# disinfection_device_control_system.net
KiCad netlist of a schematic drawn in EAGLE
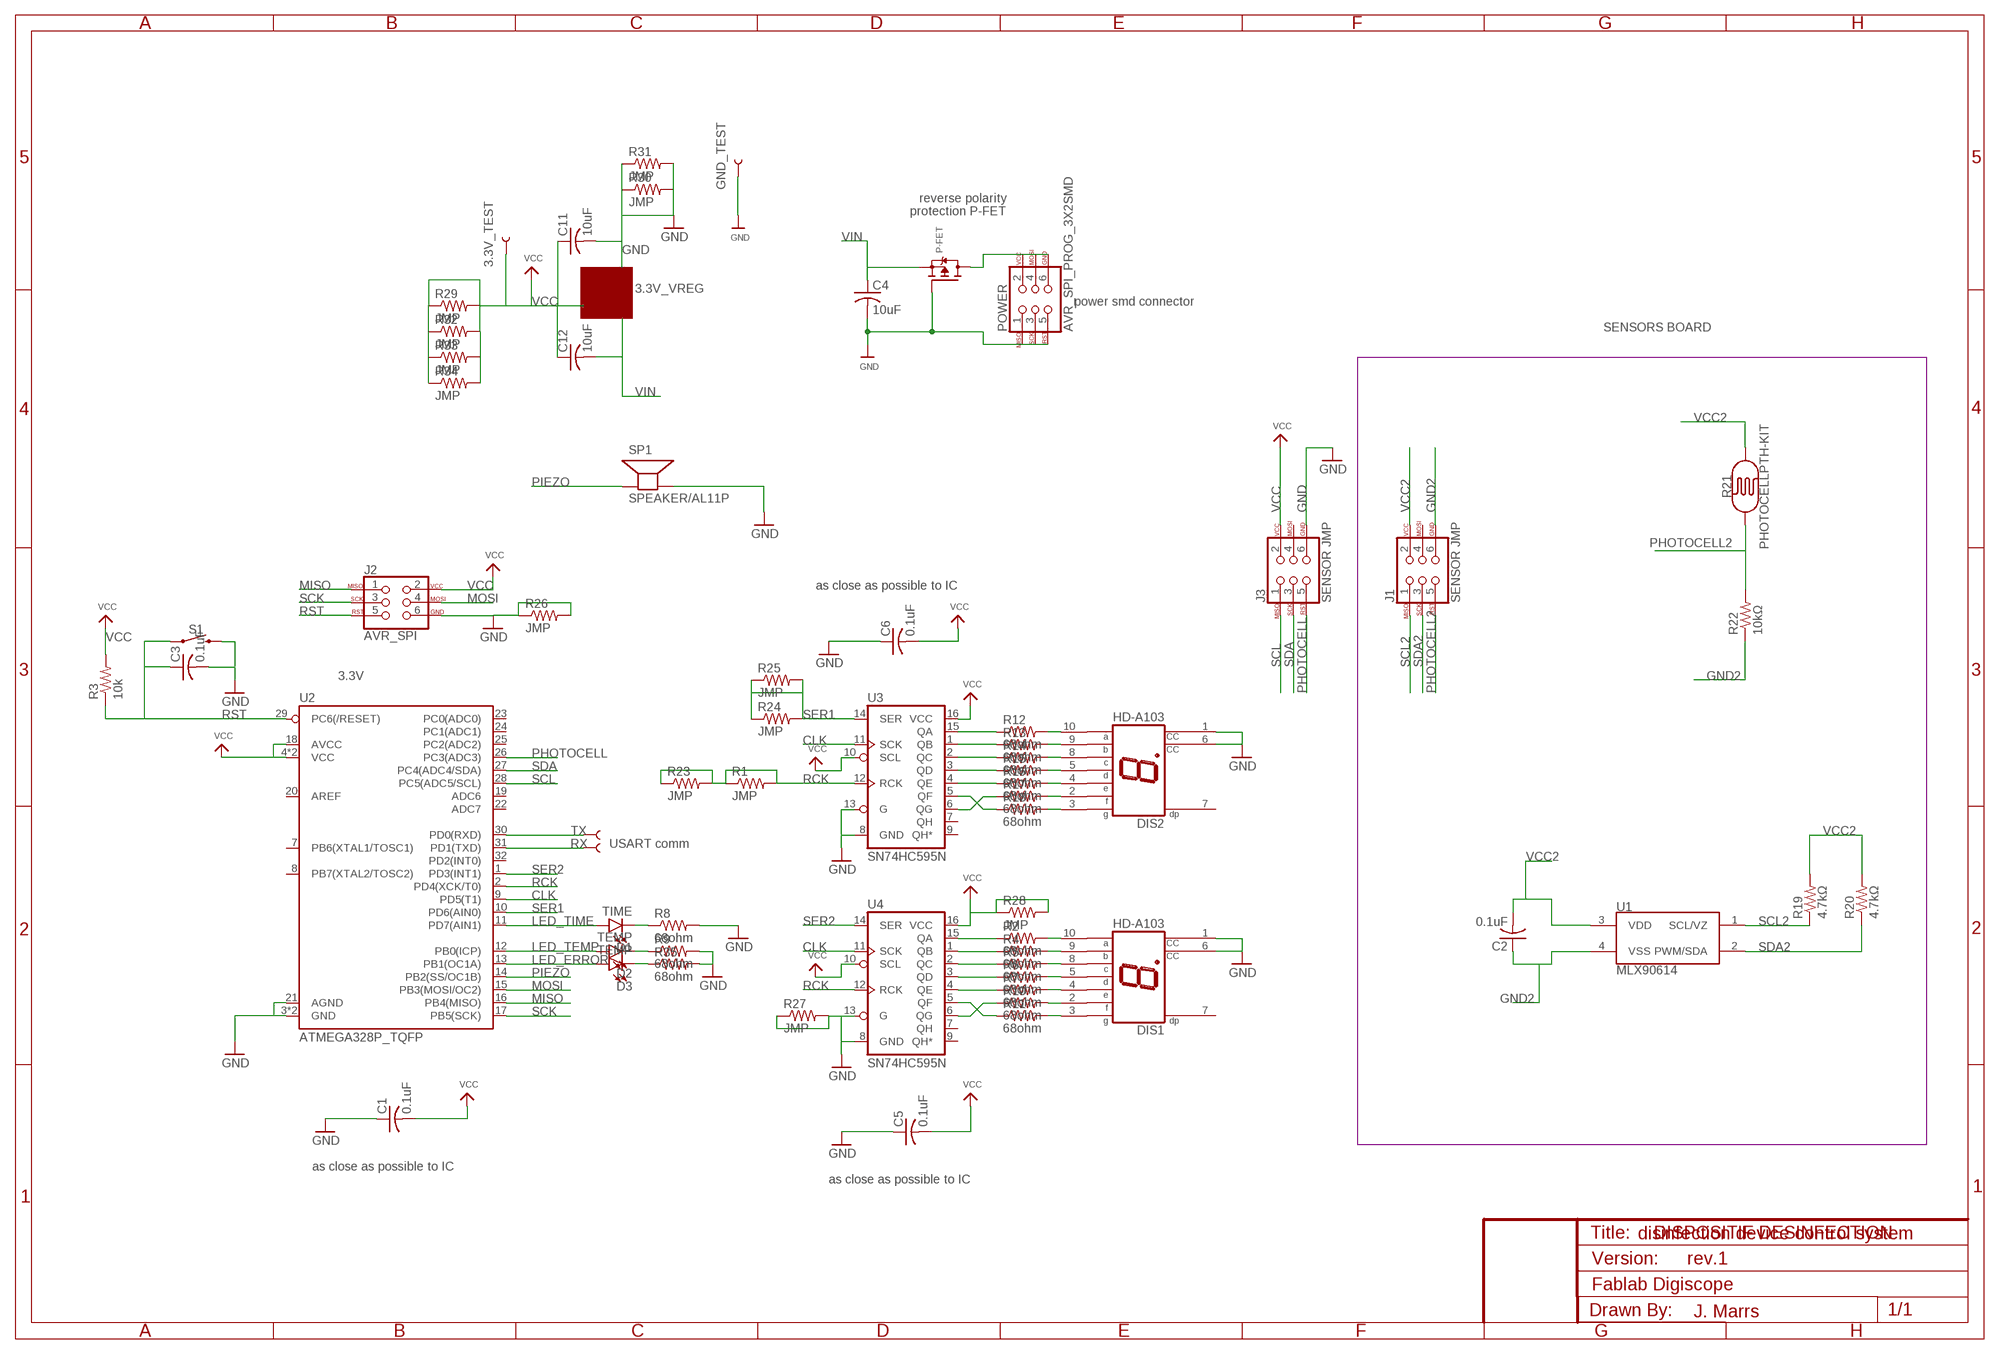
[diagram p0: schematic, sheet 1]

(export (version "E")
  (design (tool "Eeschema 10.0.6"))
  (components
    (comp (ref "3.3V_TEST")
      (value "TEST-POINT3")
      (footprint "eagle-import:PAD.03X.03")
      (libsource (lib "eagle-import") (part "TEST-POINT3"))
    )
    (comp (ref "3.3V_VREG")
      (value "MOSFET_PCH-DMG2305UX-7")
      (footprint "eagle-import:SOT23-3")
      (libsource (lib "eagle-import") (part "MOSFET_PCH-DMG2305UX-7"))
    )
    (comp (ref "C1")
      (value "0.1uF")
      (footprint "eagle-import:C1206")
      (libsource (lib "eagle-import") (part "C-USC1206"))
    )
    (comp (ref "C2")
      (value "0.1uF")
      (footprint "eagle-import:C1206")
      (libsource (lib "eagle-import") (part "C-USC1206"))
    )
    (comp (ref "C3")
      (value "0.1uF")
      (footprint "eagle-import:C1206")
      (libsource (lib "eagle-import") (part "C-USC1206"))
    )
    (comp (ref "C4")
      (value "10uF")
      (footprint "eagle-import:C1206")
      (libsource (lib "eagle-import") (part "C-USC1206"))
    )
    (comp (ref "C5")
      (value "0.1uF")
      (footprint "eagle-import:C1206")
      (libsource (lib "eagle-import") (part "C-USC1206"))
    )
    (comp (ref "C6")
      (value "0.1uF")
      (footprint "eagle-import:C1206")
      (libsource (lib "eagle-import") (part "C-USC1206"))
    )
    (comp (ref "C11")
      (value "10uF")
      (footprint "eagle-import:C1206")
      (libsource (lib "eagle-import") (part "C-USC1206"))
    )
    (comp (ref "C12")
      (value "10uF")
      (footprint "eagle-import:C1206")
      (libsource (lib "eagle-import") (part "C-USC1206"))
    )
    (comp (ref "D1")
      (value "TIME")
      (footprint "eagle-import:LED-1206")
      (libsource (lib "eagle-import") (part "LED-RED1206"))
    )
    (comp (ref "D2")
      (value "TEMP")
      (footprint "eagle-import:LED-1206")
      (libsource (lib "eagle-import") (part "LED-RED1206"))
    )
    (comp (ref "D3")
      (value "TEMP")
      (footprint "eagle-import:LED-1206")
      (libsource (lib "eagle-import") (part "LED-RED1206"))
    )
    (comp (ref "DIS1")
      (value "HD-A103")
      (footprint "eagle-import:HDSP-A")
      (libsource (lib "eagle-import") (part "HD-A103"))
    )
    (comp (ref "DIS2")
      (value "HD-A103")
      (footprint "eagle-import:HDSP-A")
      (libsource (lib "eagle-import") (part "HD-A103"))
    )
    (comp (ref "GND_TEST")
      (value "TEST-POINT3")
      (footprint "eagle-import:PAD.03X.03")
      (libsource (lib "eagle-import") (part "TEST-POINT3"))
    )
    (comp (ref "J1")
      (value "SENSOR JMP")
      (footprint "eagle-import:2X3_SMT_POSTS")
      (libsource (lib "eagle-import") (part "AVR_SPI_PROG_3X2SMD"))
    )
    (comp (ref "J2")
      (value "AVR_SPI")
      (footprint "eagle-import:2X3_SMT_POSTS")
      (libsource (lib "eagle-import") (part "AVR_SPI_PROG_3X2SMD"))
    )
    (comp (ref "J3")
      (value "SENSOR JMP")
      (footprint "eagle-import:2X3_SMT_POSTS")
      (libsource (lib "eagle-import") (part "AVR_SPI_PROG_3X2SMD"))
    )
    (comp (ref "P-FET")
      (value "MOSFET-PWIDE")
      (footprint "eagle-import:SOT23-WIDE")
      (libsource (lib "eagle-import") (part "MOSFET-PWIDE"))
    )
    (comp (ref "POWER")
      (value "AVR_SPI_PROG_3X2SMD")
      (footprint "eagle-import:2X3_SMT_POSTS")
      (libsource (lib "eagle-import") (part "AVR_SPI_PROG_3X2SMD"))
    )
    (comp (ref "R1")
      (value "JMP")
      (footprint "eagle-import:R1206")
      (libsource (lib "eagle-import") (part "R-US_R1206"))
    )
    (comp (ref "R2")
      (value "68ohm")
      (footprint "eagle-import:R1206")
      (libsource (lib "eagle-import") (part "R-US_R1206"))
    )
    (comp (ref "R3")
      (value "10k")
      (footprint "eagle-import:R1206")
      (libsource (lib "eagle-import") (part "R-US_R1206"))
    )
    (comp (ref "R4")
      (value "68ohm")
      (footprint "eagle-import:R1206")
      (libsource (lib "eagle-import") (part "R-US_R1206"))
    )
    (comp (ref "R5")
      (value "68ohm")
      (footprint "eagle-import:R1206")
      (libsource (lib "eagle-import") (part "R-US_R1206"))
    )
    (comp (ref "R6")
      (value "68ohm")
      (footprint "eagle-import:R1206")
      (libsource (lib "eagle-import") (part "R-US_R1206"))
    )
    (comp (ref "R7")
      (value "68ohm")
      (footprint "eagle-import:R1206")
      (libsource (lib "eagle-import") (part "R-US_R1206"))
    )
    (comp (ref "R8")
      (value "68ohm")
      (footprint "eagle-import:R1206")
      (libsource (lib "eagle-import") (part "R-US_R1206"))
    )
    (comp (ref "R9")
      (value "68ohm")
      (footprint "eagle-import:R1206")
      (libsource (lib "eagle-import") (part "R-US_R1206"))
    )
    (comp (ref "R10")
      (value "68ohm")
      (footprint "eagle-import:R1206")
      (libsource (lib "eagle-import") (part "R-US_R1206"))
    )
    (comp (ref "R11")
      (value "68ohm")
      (footprint "eagle-import:R1206")
      (libsource (lib "eagle-import") (part "R-US_R1206"))
    )
    (comp (ref "R12")
      (value "68ohm")
      (footprint "eagle-import:R1206")
      (libsource (lib "eagle-import") (part "R-US_R1206"))
    )
    (comp (ref "R13")
      (value "68ohm")
      (footprint "eagle-import:R1206")
      (libsource (lib "eagle-import") (part "R-US_R1206"))
    )
    (comp (ref "R14")
      (value "68ohm")
      (footprint "eagle-import:R1206")
      (libsource (lib "eagle-import") (part "R-US_R1206"))
    )
    (comp (ref "R15")
      (value "68ohm")
      (footprint "eagle-import:R1206")
      (libsource (lib "eagle-import") (part "R-US_R1206"))
    )
    (comp (ref "R16")
      (value "68ohm")
      (footprint "eagle-import:R1206")
      (libsource (lib "eagle-import") (part "R-US_R1206"))
    )
    (comp (ref "R17")
      (value "68ohm")
      (footprint "eagle-import:R1206")
      (libsource (lib "eagle-import") (part "R-US_R1206"))
    )
    (comp (ref "R18")
      (value "68ohm")
      (footprint "eagle-import:R1206")
      (libsource (lib "eagle-import") (part "R-US_R1206"))
    )
    (comp (ref "R19")
      (value "4.7kΩ")
      (footprint "eagle-import:R1206")
      (libsource (lib "eagle-import") (part "R-US_R1206"))
    )
    (comp (ref "R20")
      (value "4.7kΩ")
      (footprint "eagle-import:R1206")
      (libsource (lib "eagle-import") (part "R-US_R1206"))
    )
    (comp (ref "R21")
      (value "PHOTOCELLPTH-KIT")
      (footprint "eagle-import:PHOTOCELL-KIT")
      (libsource (lib "eagle-import") (part "PHOTOCELLPTH-KIT"))
    )
    (comp (ref "R22")
      (value "10kΩ")
      (footprint "eagle-import:R1206")
      (libsource (lib "eagle-import") (part "R-US_R1206"))
    )
    (comp (ref "R23")
      (value "JMP")
      (footprint "eagle-import:R1206")
      (libsource (lib "eagle-import") (part "R-US_R1206"))
    )
    (comp (ref "R24")
      (value "JMP")
      (footprint "eagle-import:R1206")
      (libsource (lib "eagle-import") (part "R-US_R1206"))
    )
    (comp (ref "R25")
      (value "JMP")
      (footprint "eagle-import:R1206")
      (libsource (lib "eagle-import") (part "R-US_R1206"))
    )
    (comp (ref "R26")
      (value "JMP")
      (footprint "eagle-import:R1206")
      (libsource (lib "eagle-import") (part "R-US_R1206"))
    )
    (comp (ref "R27")
      (value "JMP")
      (footprint "eagle-import:R1206")
      (libsource (lib "eagle-import") (part "R-US_R1206"))
    )
    (comp (ref "R28")
      (value "JMP")
      (footprint "eagle-import:R1206")
      (libsource (lib "eagle-import") (part "R-US_R1206"))
    )
    (comp (ref "R29")
      (value "JMP")
      (footprint "eagle-import:R1206")
      (libsource (lib "eagle-import") (part "R-US_R1206"))
    )
    (comp (ref "R30")
      (value "JMP")
      (footprint "eagle-import:R1206")
      (libsource (lib "eagle-import") (part "R-US_R1206"))
    )
    (comp (ref "R31")
      (value "JMP")
      (footprint "eagle-import:R1206")
      (libsource (lib "eagle-import") (part "R-US_R1206"))
    )
    (comp (ref "R32")
      (value "JMP")
      (footprint "eagle-import:R1206")
      (libsource (lib "eagle-import") (part "R-US_R1206"))
    )
    (comp (ref "R33")
      (value "JMP")
      (footprint "eagle-import:R1206")
      (libsource (lib "eagle-import") (part "R-US_R1206"))
    )
    (comp (ref "R34")
      (value "JMP")
      (footprint "eagle-import:R1206")
      (libsource (lib "eagle-import") (part "R-US_R1206"))
    )
    (comp (ref "R35")
      (value "68ohm")
      (footprint "eagle-import:R1206")
      (libsource (lib "eagle-import") (part "R-US_R1206"))
    )
    (comp (ref "RX")
      (value "TEST-POINT3")
      (footprint "eagle-import:PAD.03X.03")
      (libsource (lib "eagle-import") (part "TEST-POINT3"))
    )
    (comp (ref "S1")
      (value "MOMENTARY-SWITCH-SPST-PTH-6.0MM")
      (footprint "eagle-import:TACTILE_SWITCH_PTH_6.0MM")
      (libsource (lib "eagle-import") (part "MOMENTARY-SWITCH-SPST-PTH-6.0MM"))
    )
    (comp (ref "SP1")
      (value "SPEAKER/AL11P")
      (footprint "eagle-import:AL11P")
      (libsource (lib "eagle-import") (part "SPEAKER/AL11P"))
    )
    (comp (ref "TX")
      (value "TEST-POINT3")
      (footprint "eagle-import:PAD.03X.03")
      (libsource (lib "eagle-import") (part "TEST-POINT3"))
    )
    (comp (ref "U1")
      (value "MLX90614")
      (footprint "eagle-import:TO-39")
      (libsource (lib "eagle-import") (part "MLX90614"))
    )
    (comp (ref "U2")
      (value "ATMEGA328P_TQFP")
      (footprint "eagle-import:TQFP32-08")
      (libsource (lib "eagle-import") (part "ATMEGA328P_TQFP"))
    )
    (comp (ref "U3")
      (value "SN74HC595N")
      (footprint "eagle-import:DIP16")
      (libsource (lib "eagle-import") (part "74595NHC"))
    )
    (comp (ref "U4")
      (value "SN74HC595N")
      (footprint "eagle-import:DIP16")
      (libsource (lib "eagle-import") (part "74595NHC"))
    )
  )
  (nets
    (net (code "1") (name "/CLK") (class "Default")
      (node (ref "U2") (pin "9") (pinfunction "PD5(T1)_9") (pintype "bidirectional"))
      (node (ref "U3") (pin "11") (pinfunction "SCK_11") (pintype "input"))
      (node (ref "U4") (pin "11") (pinfunction "SCK_11") (pintype "input"))
    )
    (net (code "2") (name "/GND2") (class "Default")
      (node (ref "C2") (pin "1") (pinfunction "1_1") (pintype "passive"))
      (node (ref "J1") (pin "6") (pinfunction "6_6") (pintype "passive"))
      (node (ref "R22") (pin "1") (pinfunction "1_1") (pintype "passive"))
      (node (ref "U1") (pin "4") (pinfunction "VSS_4") (pintype "bidirectional"))
    )
    (net (code "3") (name "/LED_ERROR") (class "Default")
      (node (ref "D3") (pin "A") (pinfunction "A_A") (pintype "passive"))
      (node (ref "U2") (pin "13") (pinfunction "PB1(OC1A)_13") (pintype "bidirectional"))
    )
    (net (code "4") (name "/LED_TEMP") (class "Default")
      (node (ref "D2") (pin "A") (pinfunction "A_A") (pintype "passive"))
      (node (ref "U2") (pin "12") (pinfunction "PB0(ICP)_12") (pintype "bidirectional"))
    )
    (net (code "5") (name "/LED_TIME") (class "Default")
      (node (ref "D1") (pin "A") (pinfunction "A_A") (pintype "passive"))
      (node (ref "U2") (pin "11") (pinfunction "PD7(AIN1)_11") (pintype "bidirectional"))
    )
    (net (code "6") (name "/MISO") (class "Default")
      (node (ref "J2") (pin "1") (pinfunction "1_1") (pintype "passive"))
      (node (ref "U2") (pin "16") (pinfunction "PB4(MISO)_16") (pintype "bidirectional"))
    )
    (net (code "7") (name "/MOSI") (class "Default")
      (node (ref "J2") (pin "4") (pinfunction "4_4") (pintype "passive"))
      (node (ref "U2") (pin "15") (pinfunction "PB3(MOSI/OC2)_15") (pintype "bidirectional"))
    )
    (net (code "8") (name "/PHOTOCELL") (class "Default")
      (node (ref "J3") (pin "5") (pinfunction "5_5") (pintype "passive"))
      (node (ref "U2") (pin "26") (pinfunction "PC3(ADC3)_26") (pintype "bidirectional"))
    )
    (net (code "9") (name "/PHOTOCELL2") (class "Default")
      (node (ref "J1") (pin "5") (pinfunction "5_5") (pintype "passive"))
      (node (ref "R21") (pin "1") (pinfunction "P$1_1") (pintype "bidirectional"))
      (node (ref "R22") (pin "2") (pinfunction "2_2") (pintype "passive"))
    )
    (net (code "10") (name "/PIEZO") (class "Default")
      (node (ref "SP1") (pin "+") (pinfunction "+_+") (pintype "passive"))
      (node (ref "U2") (pin "14") (pinfunction "PB2(SS/OC1B)_14") (pintype "bidirectional"))
    )
    (net (code "11") (name "/RCK") (class "Default")
      (node (ref "R1") (pin "1") (pinfunction "1_1") (pintype "passive"))
      (node (ref "R1") (pin "2") (pinfunction "2_2") (pintype "passive"))
      (node (ref "R23") (pin "1") (pinfunction "1_1") (pintype "passive"))
      (node (ref "R23") (pin "2") (pinfunction "2_2") (pintype "passive"))
      (node (ref "U2") (pin "2") (pinfunction "PD4(XCK/T0)_2") (pintype "bidirectional"))
      (node (ref "U3") (pin "12") (pinfunction "RCK_12") (pintype "input"))
      (node (ref "U4") (pin "12") (pinfunction "RCK_12") (pintype "input"))
    )
    (net (code "12") (name "/RST") (class "Default")
      (node (ref "C3") (pin "1") (pinfunction "1_1") (pintype "passive"))
      (node (ref "J2") (pin "5") (pinfunction "5_5") (pintype "passive"))
      (node (ref "R3") (pin "1") (pinfunction "1_1") (pintype "passive"))
      (node (ref "S1") (pin "1") (pinfunction "1_1") (pintype "passive"))
      (node (ref "U2") (pin "29") (pinfunction "PC6(/RESET)_29") (pintype "bidirectional"))
    )
    (net (code "13") (name "/SCK") (class "Default")
      (node (ref "J2") (pin "3") (pinfunction "3_3") (pintype "passive"))
      (node (ref "U2") (pin "17") (pinfunction "PB5(SCK)_17") (pintype "bidirectional"))
    )
    (net (code "14") (name "/SCL") (class "Default")
      (node (ref "J3") (pin "1") (pinfunction "1_1") (pintype "passive"))
      (node (ref "U2") (pin "28") (pinfunction "PC5(ADC5/SCL)_28") (pintype "bidirectional"))
    )
    (net (code "15") (name "/SCL2") (class "Default")
      (node (ref "J1") (pin "1") (pinfunction "1_1") (pintype "passive"))
      (node (ref "R19") (pin "1") (pinfunction "1_1") (pintype "passive"))
      (node (ref "U1") (pin "1") (pinfunction "SCL/VZ_1") (pintype "bidirectional"))
    )
    (net (code "16") (name "/SDA") (class "Default")
      (node (ref "J3") (pin "3") (pinfunction "3_3") (pintype "passive"))
      (node (ref "U2") (pin "27") (pinfunction "PC4(ADC4/SDA)_27") (pintype "bidirectional"))
    )
    (net (code "17") (name "/SDA2") (class "Default")
      (node (ref "J1") (pin "3") (pinfunction "3_3") (pintype "passive"))
      (node (ref "R20") (pin "1") (pinfunction "1_1") (pintype "passive"))
      (node (ref "U1") (pin "2") (pinfunction "PWM/SDA_2") (pintype "bidirectional"))
    )
    (net (code "18") (name "/SER1") (class "Default")
      (node (ref "R24") (pin "1") (pinfunction "1_1") (pintype "passive"))
      (node (ref "R24") (pin "2") (pinfunction "2_2") (pintype "passive"))
      (node (ref "R25") (pin "1") (pinfunction "1_1") (pintype "passive"))
      (node (ref "R25") (pin "2") (pinfunction "2_2") (pintype "passive"))
      (node (ref "U2") (pin "10") (pinfunction "PD6(AIN0)_10") (pintype "bidirectional"))
      (node (ref "U3") (pin "14") (pinfunction "SER_14") (pintype "input"))
    )
    (net (code "19") (name "/SER2") (class "Default")
      (node (ref "U2") (pin "1") (pinfunction "PD3(INT1)_1") (pintype "bidirectional"))
      (node (ref "U4") (pin "14") (pinfunction "SER_14") (pintype "input"))
    )
    (net (code "20") (name "/VCC2") (class "Default")
      (node (ref "C2") (pin "2") (pinfunction "2_2") (pintype "passive"))
      (node (ref "J1") (pin "2") (pinfunction "2_2") (pintype "passive"))
      (node (ref "R19") (pin "2") (pinfunction "2_2") (pintype "passive"))
      (node (ref "R20") (pin "2") (pinfunction "2_2") (pintype "passive"))
      (node (ref "R21") (pin "2") (pinfunction "P$2_2") (pintype "bidirectional"))
      (node (ref "U1") (pin "3") (pinfunction "VDD_3") (pintype "bidirectional"))
    )
    (net (code "21") (name "/VIN") (class "Default")
      (node (ref "3.3V_VREG") (pin "2") (pinfunction "S_2") (pintype "bidirectional"))
      (node (ref "C12") (pin "2") (pinfunction "2_2") (pintype "passive"))
      (node (ref "C4") (pin "1") (pinfunction "1_1") (pintype "passive"))
      (node (ref "P-FET") (pin "2") (pinfunction "S_2") (pintype "passive"))
    )
    (net (code "22") (name "GND") (class "Default")
      (node (ref "3.3V_VREG") (pin "3") (pinfunction "D_3") (pintype "bidirectional"))
      (node (ref "C1") (pin "1") (pinfunction "1_1") (pintype "passive"))
      (node (ref "C11") (pin "2") (pinfunction "2_2") (pintype "passive"))
      (node (ref "C3") (pin "2") (pinfunction "2_2") (pintype "passive"))
      (node (ref "C4") (pin "2") (pinfunction "2_2") (pintype "passive"))
      (node (ref "C5") (pin "1") (pinfunction "1_1") (pintype "passive"))
      (node (ref "C6") (pin "1") (pinfunction "1_1") (pintype "passive"))
      (node (ref "DIS1") (pin "1") (pinfunction "CC_1") (pintype "passive"))
      (node (ref "DIS1") (pin "6") (pinfunction "CC_6") (pintype "passive"))
      (node (ref "DIS2") (pin "1") (pinfunction "CC_1") (pintype "passive"))
      (node (ref "DIS2") (pin "6") (pinfunction "CC_6") (pintype "passive"))
      (node (ref "GND_TEST") (pin "P$1") (pinfunction "1_P$1") (pintype "bidirectional"))
      (node (ref "J2") (pin "6") (pinfunction "6_6") (pintype "passive"))
      (node (ref "J3") (pin "6") (pinfunction "6_6") (pintype "passive"))
      (node (ref "P-FET") (pin "1") (pinfunction "G_1") (pintype "passive"))
      (node (ref "POWER") (pin "1") (pinfunction "1_1") (pintype "passive"))
      (node (ref "POWER") (pin "3") (pinfunction "3_3") (pintype "passive"))
      (node (ref "POWER") (pin "5") (pinfunction "5_5") (pintype "passive"))
      (node (ref "R26") (pin "1") (pinfunction "1_1") (pintype "passive"))
      (node (ref "R26") (pin "2") (pinfunction "2_2") (pintype "passive"))
      (node (ref "R27") (pin "1") (pinfunction "1_1") (pintype "passive"))
      (node (ref "R27") (pin "2") (pinfunction "2_2") (pintype "passive"))
      (node (ref "R30") (pin "1") (pinfunction "1_1") (pintype "passive"))
      (node (ref "R30") (pin "2") (pinfunction "2_2") (pintype "passive"))
      (node (ref "R31") (pin "1") (pinfunction "1_1") (pintype "passive"))
      (node (ref "R31") (pin "2") (pinfunction "2_2") (pintype "passive"))
      (node (ref "R35") (pin "2") (pinfunction "2_2") (pintype "passive"))
      (node (ref "R8") (pin "2") (pinfunction "2_2") (pintype "passive"))
      (node (ref "R9") (pin "2") (pinfunction "2_2") (pintype "passive"))
      (node (ref "S1") (pin "3") (pinfunction "2_3") (pintype "passive"))
      (node (ref "SP1") (pin "-") (pinfunction "-_-") (pintype "passive"))
      (node (ref "U2") (pin "21") (pinfunction "AGND_21") (pintype "bidirectional"))
      (node (ref "U2") (pin "3") (pinfunction "GND_3") (pintype "bidirectional"))
      (node (ref "U2") (pin "5") (pinfunction "GND_5") (pintype "bidirectional"))
      (node (ref "U3") (pin "13") (pinfunction "G_13") (pintype "input"))
      (node (ref "U3") (pin "8") (pinfunction "GND_8") (pintype "power_in"))
      (node (ref "U4") (pin "13") (pinfunction "G_13") (pintype "input"))
      (node (ref "U4") (pin "8") (pinfunction "GND_8") (pintype "power_in"))
    )
    (net (code "23") (name "Net-(D1-PadC)") (class "Default")
      (node (ref "D1") (pin "C") (pinfunction "C_C") (pintype "passive"))
      (node (ref "R8") (pin "1") (pinfunction "1_1") (pintype "passive"))
    )
    (net (code "24") (name "Net-(D2-PadC)") (class "Default")
      (node (ref "D2") (pin "C") (pinfunction "C_C") (pintype "passive"))
      (node (ref "R9") (pin "1") (pinfunction "1_1") (pintype "passive"))
    )
    (net (code "25") (name "Net-(D3-PadC)") (class "Default")
      (node (ref "D3") (pin "C") (pinfunction "C_C") (pintype "passive"))
      (node (ref "R35") (pin "1") (pinfunction "1_1") (pintype "passive"))
    )
    (net (code "26") (name "Net-(DIS1-A)") (class "Default")
      (node (ref "DIS1") (pin "10") (pinfunction "A_10") (pintype "passive"))
      (node (ref "R2") (pin "2") (pinfunction "2_2") (pintype "passive"))
    )
    (net (code "27") (name "Net-(DIS1-B)") (class "Default")
      (node (ref "DIS1") (pin "9") (pinfunction "B_9") (pintype "passive"))
      (node (ref "R4") (pin "2") (pinfunction "2_2") (pintype "passive"))
    )
    (net (code "28") (name "Net-(DIS1-C)") (class "Default")
      (node (ref "DIS1") (pin "8") (pinfunction "C_8") (pintype "passive"))
      (node (ref "R5") (pin "2") (pinfunction "2_2") (pintype "passive"))
    )
    (net (code "29") (name "Net-(DIS1-D)") (class "Default")
      (node (ref "DIS1") (pin "5") (pinfunction "D_5") (pintype "passive"))
      (node (ref "R6") (pin "2") (pinfunction "2_2") (pintype "passive"))
    )
    (net (code "30") (name "Net-(DIS1-E)") (class "Default")
      (node (ref "DIS1") (pin "4") (pinfunction "E_4") (pintype "passive"))
      (node (ref "R7") (pin "2") (pinfunction "2_2") (pintype "passive"))
    )
    (net (code "31") (name "Net-(DIS1-F)") (class "Default")
      (node (ref "DIS1") (pin "2") (pinfunction "F_2") (pintype "passive"))
      (node (ref "R10") (pin "2") (pinfunction "2_2") (pintype "passive"))
    )
    (net (code "32") (name "Net-(DIS1-G)") (class "Default")
      (node (ref "DIS1") (pin "3") (pinfunction "G_3") (pintype "passive"))
      (node (ref "R11") (pin "2") (pinfunction "2_2") (pintype "passive"))
    )
    (net (code "33") (name "Net-(DIS2-A)") (class "Default")
      (node (ref "DIS2") (pin "10") (pinfunction "A_10") (pintype "passive"))
      (node (ref "R12") (pin "2") (pinfunction "2_2") (pintype "passive"))
    )
    (net (code "34") (name "Net-(DIS2-B)") (class "Default")
      (node (ref "DIS2") (pin "9") (pinfunction "B_9") (pintype "passive"))
      (node (ref "R13") (pin "2") (pinfunction "2_2") (pintype "passive"))
    )
    (net (code "35") (name "Net-(DIS2-C)") (class "Default")
      (node (ref "DIS2") (pin "8") (pinfunction "C_8") (pintype "passive"))
      (node (ref "R14") (pin "2") (pinfunction "2_2") (pintype "passive"))
    )
    (net (code "36") (name "Net-(DIS2-D)") (class "Default")
      (node (ref "DIS2") (pin "5") (pinfunction "D_5") (pintype "passive"))
      (node (ref "R15") (pin "2") (pinfunction "2_2") (pintype "passive"))
    )
    (net (code "37") (name "Net-(DIS2-E)") (class "Default")
      (node (ref "DIS2") (pin "4") (pinfunction "E_4") (pintype "passive"))
      (node (ref "R16") (pin "2") (pinfunction "2_2") (pintype "passive"))
    )
    (net (code "38") (name "Net-(DIS2-F)") (class "Default")
      (node (ref "DIS2") (pin "2") (pinfunction "F_2") (pintype "passive"))
      (node (ref "R17") (pin "2") (pinfunction "2_2") (pintype "passive"))
    )
    (net (code "39") (name "Net-(DIS2-G)") (class "Default")
      (node (ref "DIS2") (pin "3") (pinfunction "G_3") (pintype "passive"))
      (node (ref "R18") (pin "2") (pinfunction "2_2") (pintype "passive"))
    )
    (net (code "40") (name "Net-(P-FET-D)") (class "Default")
      (node (ref "P-FET") (pin "3") (pinfunction "D_3") (pintype "passive"))
      (node (ref "POWER") (pin "2") (pinfunction "2_2") (pintype "passive"))
      (node (ref "POWER") (pin "4") (pinfunction "4_4") (pintype "passive"))
      (node (ref "POWER") (pin "6") (pinfunction "6_6") (pintype "passive"))
    )
    (net (code "41") (name "Net-(RX-1)") (class "Default")
      (node (ref "RX") (pin "P$1") (pinfunction "1_P$1") (pintype "bidirectional"))
      (node (ref "U2") (pin "31") (pinfunction "PD1(TXD)_31") (pintype "bidirectional"))
    )
    (net (code "42") (name "Net-(TX-1)") (class "Default")
      (node (ref "TX") (pin "P$1") (pinfunction "1_P$1") (pintype "bidirectional"))
      (node (ref "U2") (pin "30") (pinfunction "PD0(RXD)_30") (pintype "bidirectional"))
    )
    (net (code "43") (name "Net-(U3-QA)") (class "Default")
      (node (ref "R12") (pin "1") (pinfunction "1_1") (pintype "passive"))
      (node (ref "U3") (pin "15") (pinfunction "QA_15") (pintype "tri_state"))
    )
    (net (code "44") (name "Net-(U3-QB)") (class "Default")
      (node (ref "R13") (pin "1") (pinfunction "1_1") (pintype "passive"))
      (node (ref "U3") (pin "1") (pinfunction "QB_1") (pintype "tri_state"))
    )
    (net (code "45") (name "Net-(U3-QC)") (class "Default")
      (node (ref "R14") (pin "1") (pinfunction "1_1") (pintype "passive"))
      (node (ref "U3") (pin "2") (pinfunction "QC_2") (pintype "tri_state"))
    )
    (net (code "46") (name "Net-(U3-QD)") (class "Default")
      (node (ref "R15") (pin "1") (pinfunction "1_1") (pintype "passive"))
      (node (ref "U3") (pin "3") (pinfunction "QD_3") (pintype "tri_state"))
    )
    (net (code "47") (name "Net-(U3-QE)") (class "Default")
      (node (ref "R16") (pin "1") (pinfunction "1_1") (pintype "passive"))
      (node (ref "U3") (pin "4") (pinfunction "QE_4") (pintype "tri_state"))
    )
    (net (code "48") (name "Net-(U3-QF)") (class "Default")
      (node (ref "R18") (pin "1") (pinfunction "1_1") (pintype "passive"))
      (node (ref "U3") (pin "5") (pinfunction "QF_5") (pintype "tri_state"))
    )
    (net (code "49") (name "Net-(U3-QG)") (class "Default")
      (node (ref "R17") (pin "1") (pinfunction "1_1") (pintype "passive"))
      (node (ref "U3") (pin "6") (pinfunction "QG_6") (pintype "tri_state"))
    )
    (net (code "50") (name "Net-(U4-QA)") (class "Default")
      (node (ref "R2") (pin "1") (pinfunction "1_1") (pintype "passive"))
      (node (ref "U4") (pin "15") (pinfunction "QA_15") (pintype "tri_state"))
    )
    (net (code "51") (name "Net-(U4-QB)") (class "Default")
      (node (ref "R4") (pin "1") (pinfunction "1_1") (pintype "passive"))
      (node (ref "U4") (pin "1") (pinfunction "QB_1") (pintype "tri_state"))
    )
    (net (code "52") (name "Net-(U4-QC)") (class "Default")
      (node (ref "R5") (pin "1") (pinfunction "1_1") (pintype "passive"))
      (node (ref "U4") (pin "2") (pinfunction "QC_2") (pintype "tri_state"))
    )
    (net (code "53") (name "Net-(U4-QD)") (class "Default")
      (node (ref "R6") (pin "1") (pinfunction "1_1") (pintype "passive"))
      (node (ref "U4") (pin "3") (pinfunction "QD_3") (pintype "tri_state"))
    )
    (net (code "54") (name "Net-(U4-QE)") (class "Default")
      (node (ref "R7") (pin "1") (pinfunction "1_1") (pintype "passive"))
      (node (ref "U4") (pin "4") (pinfunction "QE_4") (pintype "tri_state"))
    )
    (net (code "55") (name "Net-(U4-QF)") (class "Default")
      (node (ref "R11") (pin "1") (pinfunction "1_1") (pintype "passive"))
      (node (ref "U4") (pin "5") (pinfunction "QF_5") (pintype "tri_state"))
    )
    (net (code "56") (name "Net-(U4-QG)") (class "Default")
      (node (ref "R10") (pin "1") (pinfunction "1_1") (pintype "passive"))
      (node (ref "U4") (pin "6") (pinfunction "QG_6") (pintype "tri_state"))
    )
    (net (code "57") (name "VCC") (class "Default")
      (node (ref "3.3V_TEST") (pin "P$1") (pinfunction "1_P$1") (pintype "bidirectional"))
      (node (ref "3.3V_VREG") (pin "1") (pinfunction "G_1") (pintype "bidirectional"))
      (node (ref "C1") (pin "2") (pinfunction "2_2") (pintype "passive"))
      (node (ref "C11") (pin "1") (pinfunction "1_1") (pintype "passive"))
      (node (ref "C12") (pin "1") (pinfunction "1_1") (pintype "passive"))
      (node (ref "C5") (pin "2") (pinfunction "2_2") (pintype "passive"))
      (node (ref "C6") (pin "2") (pinfunction "2_2") (pintype "passive"))
      (node (ref "J2") (pin "2") (pinfunction "2_2") (pintype "passive"))
      (node (ref "J3") (pin "2") (pinfunction "2_2") (pintype "passive"))
      (node (ref "R28") (pin "1") (pinfunction "1_1") (pintype "passive"))
      (node (ref "R28") (pin "2") (pinfunction "2_2") (pintype "passive"))
      (node (ref "R29") (pin "1") (pinfunction "1_1") (pintype "passive"))
      (node (ref "R29") (pin "2") (pinfunction "2_2") (pintype "passive"))
      (node (ref "R3") (pin "2") (pinfunction "2_2") (pintype "passive"))
      (node (ref "R32") (pin "1") (pinfunction "1_1") (pintype "passive"))
      (node (ref "R32") (pin "2") (pinfunction "2_2") (pintype "passive"))
      (node (ref "R33") (pin "1") (pinfunction "1_1") (pintype "passive"))
      (node (ref "R33") (pin "2") (pinfunction "2_2") (pintype "passive"))
      (node (ref "R34") (pin "1") (pinfunction "1_1") (pintype "passive"))
      (node (ref "R34") (pin "2") (pinfunction "2_2") (pintype "passive"))
      (node (ref "U2") (pin "18") (pinfunction "AVCC_18") (pintype "bidirectional"))
      (node (ref "U2") (pin "4") (pinfunction "VCC_4") (pintype "bidirectional"))
      (node (ref "U2") (pin "6") (pinfunction "VCC_6") (pintype "bidirectional"))
      (node (ref "U3") (pin "10") (pinfunction "SCL_10") (pintype "input"))
      (node (ref "U3") (pin "16") (pinfunction "VCC_16") (pintype "power_in"))
      (node (ref "U4") (pin "10") (pinfunction "SCL_10") (pintype "input"))
      (node (ref "U4") (pin "16") (pinfunction "VCC_16") (pintype "power_in"))
    )
    (net (code "58") (name "unconnected-(DIS1-DP-Pad7)") (class "Default")
      (node (ref "DIS1") (pin "7") (pinfunction "DP_7") (pintype "passive"))
    )
    (net (code "59") (name "unconnected-(DIS2-DP-Pad7)") (class "Default")
      (node (ref "DIS2") (pin "7") (pinfunction "DP_7") (pintype "passive"))
    )
    (net (code "60") (name "unconnected-(J1-Pad4)") (class "Default")
      (node (ref "J1") (pin "4") (pinfunction "4_4") (pintype "passive"))
    )
    (net (code "61") (name "unconnected-(J3-Pad4)") (class "Default")
      (node (ref "J3") (pin "4") (pinfunction "4_4") (pintype "passive"))
    )
    (net (code "62") (name "unconnected-(U2-ADC6-Pad19)") (class "Default")
      (node (ref "U2") (pin "19") (pinfunction "ADC6_19") (pintype "bidirectional"))
    )
    (net (code "63") (name "unconnected-(U2-ADC7-Pad22)") (class "Default")
      (node (ref "U2") (pin "22") (pinfunction "ADC7_22") (pintype "bidirectional"))
    )
    (net (code "64") (name "unconnected-(U2-AREF-Pad20)") (class "Default")
      (node (ref "U2") (pin "20") (pinfunction "AREF_20") (pintype "bidirectional"))
    )
    (net (code "65") (name "unconnected-(U2-PB6(XTAL1{slash}TOSC1)-Pad7)") (class "Default")
      (node (ref "U2") (pin "7") (pinfunction "PB6(XTAL1/TOSC1)_7") (pintype "bidirectional"))
    )
    (net (code "66") (name "unconnected-(U2-PB7(XTAL2{slash}TOSC2)-Pad8)") (class "Default")
      (node (ref "U2") (pin "8") (pinfunction "PB7(XTAL2/TOSC2)_8") (pintype "bidirectional"))
    )
    (net (code "67") (name "unconnected-(U2-PC0(ADC0)-Pad23)") (class "Default")
      (node (ref "U2") (pin "23") (pinfunction "PC0(ADC0)_23") (pintype "bidirectional"))
    )
    (net (code "68") (name "unconnected-(U2-PC1(ADC1)-Pad24)") (class "Default")
      (node (ref "U2") (pin "24") (pinfunction "PC1(ADC1)_24") (pintype "bidirectional"))
    )
    (net (code "69") (name "unconnected-(U2-PC2(ADC2)-Pad25)") (class "Default")
      (node (ref "U2") (pin "25") (pinfunction "PC2(ADC2)_25") (pintype "bidirectional"))
    )
    (net (code "70") (name "unconnected-(U2-PD2(INT0)-Pad32)") (class "Default")
      (node (ref "U2") (pin "32") (pinfunction "PD2(INT0)_32") (pintype "bidirectional"))
    )
    (net (code "71") (name "unconnected-(U3-QH*-Pad9)") (class "Default")
      (node (ref "U3") (pin "9") (pinfunction "QH*_9") (pintype "tri_state"))
    )
    (net (code "72") (name "unconnected-(U3-QH-Pad7)") (class "Default")
      (node (ref "U3") (pin "7") (pinfunction "QH_7") (pintype "tri_state"))
    )
    (net (code "73") (name "unconnected-(U4-QH*-Pad9)") (class "Default")
      (node (ref "U4") (pin "9") (pinfunction "QH*_9") (pintype "tri_state"))
    )
    (net (code "74") (name "unconnected-(U4-QH-Pad7)") (class "Default")
      (node (ref "U4") (pin "7") (pinfunction "QH_7") (pintype "tri_state"))
    )
  )
)
